# Wattuino-RC_v10.net
KiCad netlist of a schematic drawn in EAGLE
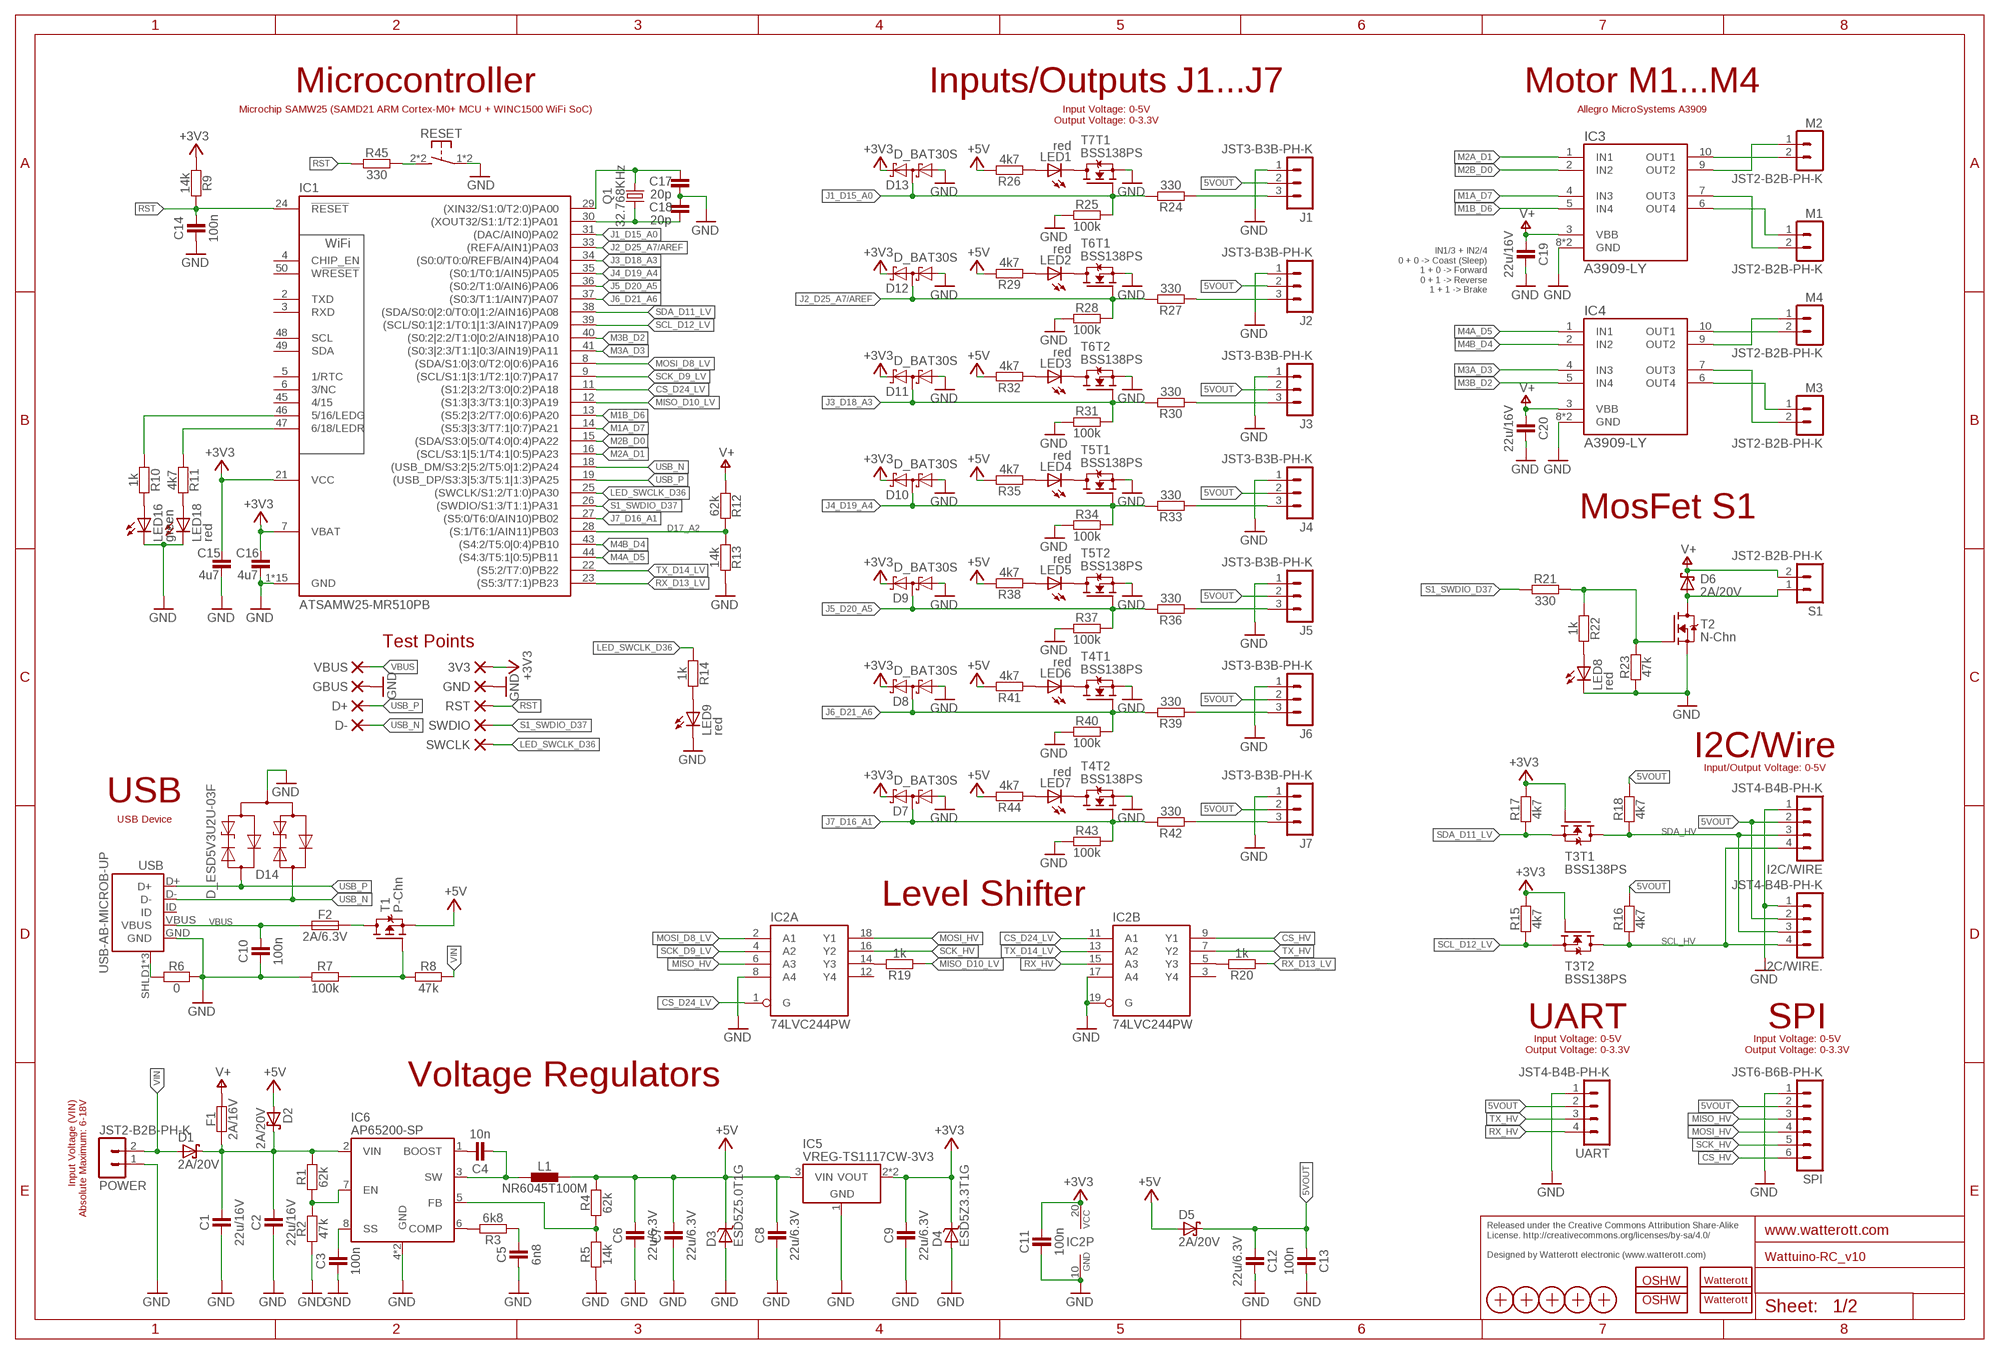
[diagram p0: schematic, sheet 1]
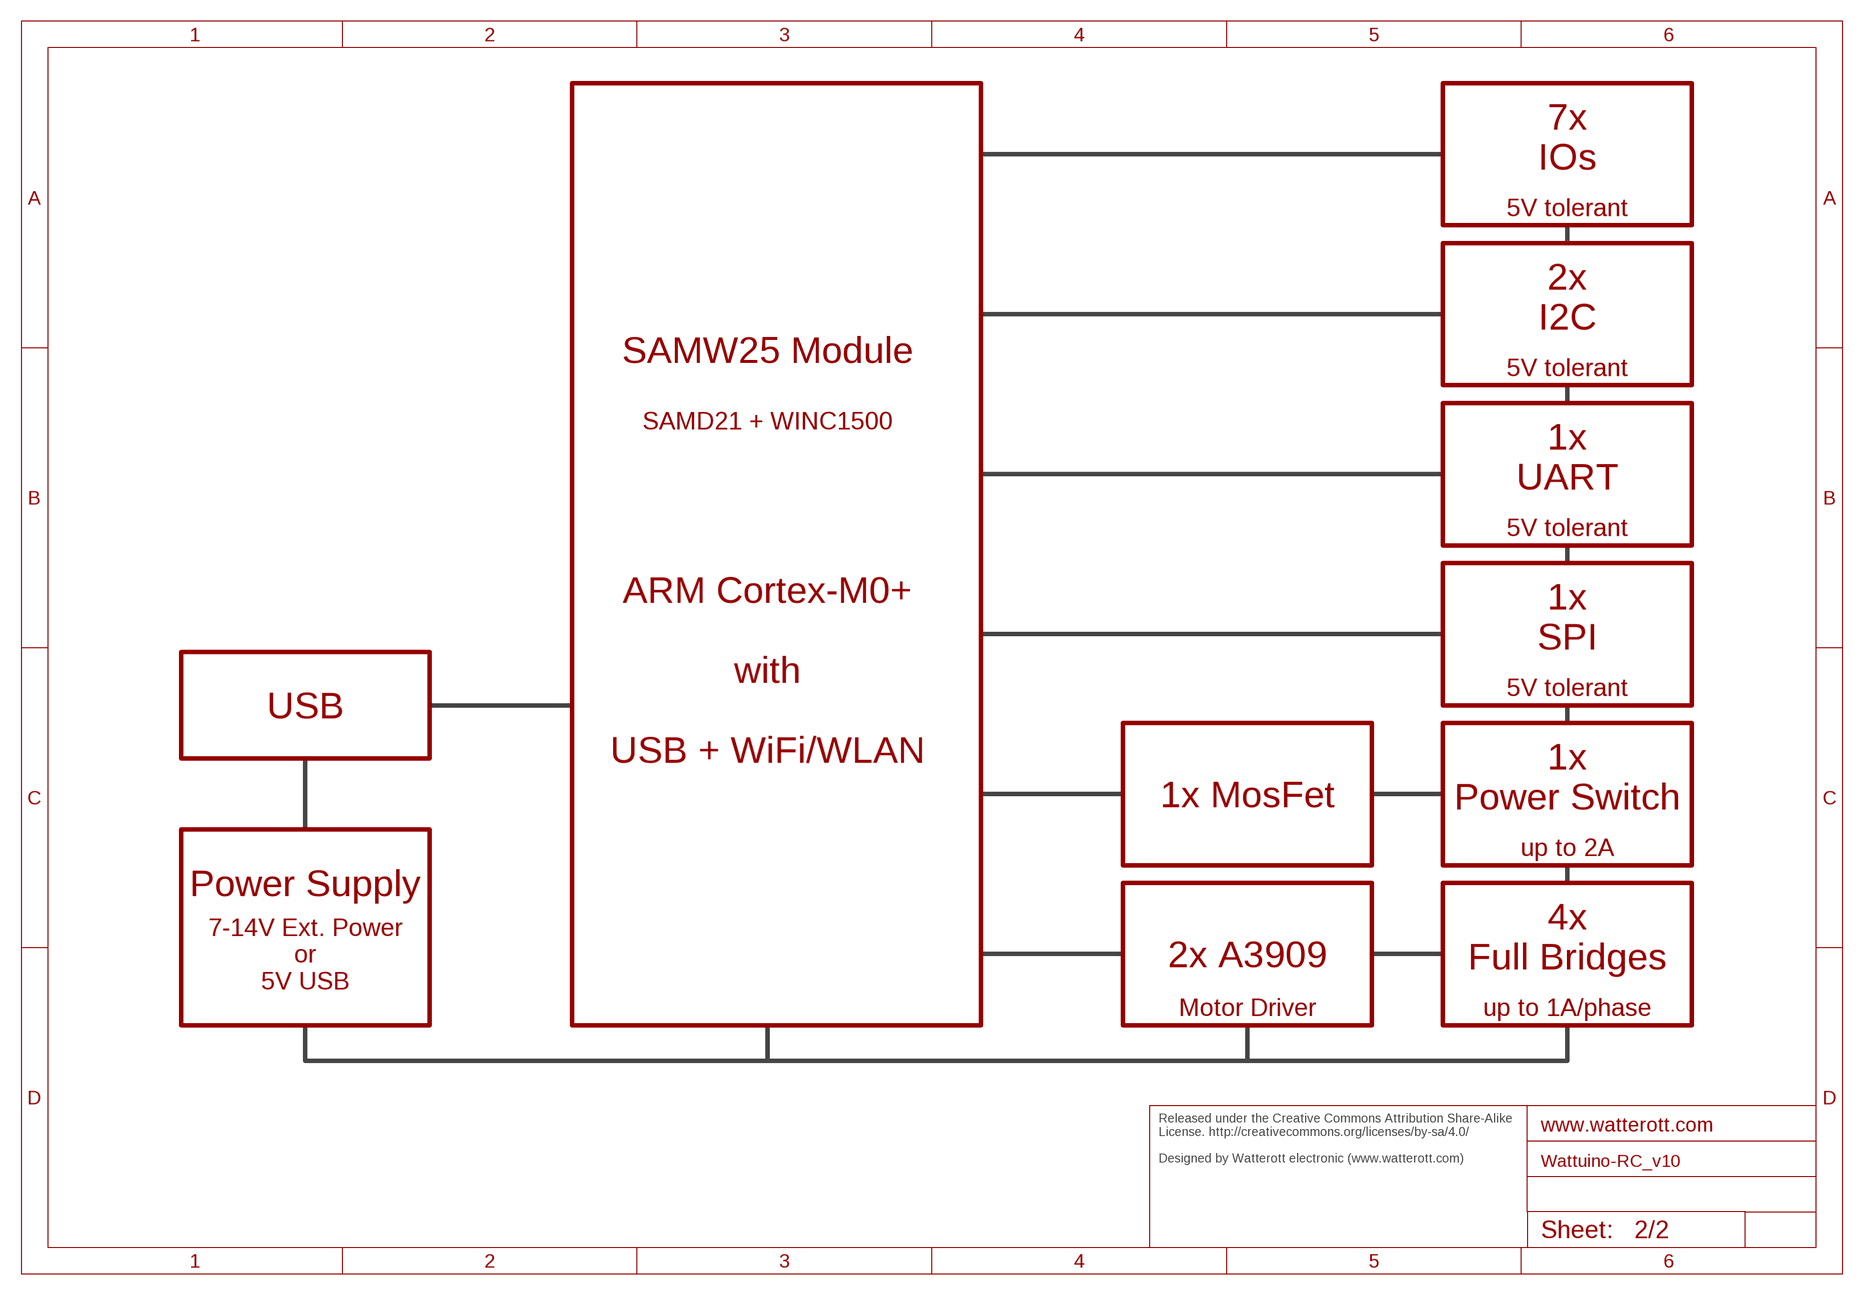
[diagram p1: schematic, sheet 2]

(export (version "E")
  (design (tool "Eeschema 10.0.6"))
  (components
    (comp (ref "3V3")
      (value "PAD-1.0_NC")
      (footprint "eagle-import:PAD-1.0_NC")
      (libsource (lib "eagle-import") (part "PAD-1.0_NC"))
    )
    (comp (ref "C1")
      (value "22u/16V")
      (footprint "eagle-import:C0805")
      (libsource (lib "eagle-import") (part "CAPACITOR-0805"))
    )
    (comp (ref "C2")
      (value "22u/16V")
      (footprint "eagle-import:C0805")
      (libsource (lib "eagle-import") (part "CAPACITOR-0805"))
    )
    (comp (ref "C3")
      (value "100n")
      (footprint "eagle-import:C0402")
      (libsource (lib "eagle-import") (part "CAPACITOR-0402"))
    )
    (comp (ref "C4")
      (value "10n")
      (footprint "eagle-import:C0402")
      (libsource (lib "eagle-import") (part "CAPACITOR-0402"))
    )
    (comp (ref "C5")
      (value "6n8")
      (footprint "eagle-import:C0402")
      (libsource (lib "eagle-import") (part "CAPACITOR-0402"))
    )
    (comp (ref "C6")
      (value "22u/6.3V")
      (footprint "eagle-import:C0805")
      (libsource (lib "eagle-import") (part "CAPACITOR-0805"))
    )
    (comp (ref "C7")
      (value "22u/6.3V")
      (footprint "eagle-import:C0805")
      (libsource (lib "eagle-import") (part "CAPACITOR-0805"))
    )
    (comp (ref "C8")
      (value "22u/6.3V")
      (footprint "eagle-import:C0805")
      (libsource (lib "eagle-import") (part "CAPACITOR-0805"))
    )
    (comp (ref "C9")
      (value "22u/6.3V")
      (footprint "eagle-import:C0805")
      (libsource (lib "eagle-import") (part "CAPACITOR-0805"))
    )
    (comp (ref "C10")
      (value "100n")
      (footprint "eagle-import:C0402")
      (libsource (lib "eagle-import") (part "CAPACITOR-0402"))
    )
    (comp (ref "C11")
      (value "100n")
      (footprint "eagle-import:C0402")
      (libsource (lib "eagle-import") (part "CAPACITOR-0402"))
    )
    (comp (ref "C12")
      (value "22u/6.3V")
      (footprint "eagle-import:C0805")
      (libsource (lib "eagle-import") (part "CAPACITOR-0805"))
    )
    (comp (ref "C13")
      (value "100n")
      (footprint "eagle-import:C0402")
      (libsource (lib "eagle-import") (part "CAPACITOR-0402"))
    )
    (comp (ref "C14")
      (value "100n")
      (footprint "eagle-import:C0402")
      (libsource (lib "eagle-import") (part "CAPACITOR-0402"))
    )
    (comp (ref "C15")
      (value "4u7")
      (footprint "eagle-import:C0603")
      (libsource (lib "eagle-import") (part "CAPACITOR-0603"))
    )
    (comp (ref "C16")
      (value "4u7")
      (footprint "eagle-import:C0603")
      (libsource (lib "eagle-import") (part "CAPACITOR-0603"))
    )
    (comp (ref "C17")
      (value "20p")
      (footprint "eagle-import:C0402")
      (libsource (lib "eagle-import") (part "CAPACITOR-0402"))
    )
    (comp (ref "C18")
      (value "20p")
      (footprint "eagle-import:C0402")
      (libsource (lib "eagle-import") (part "CAPACITOR-0402"))
    )
    (comp (ref "C19")
      (value "22u/16V")
      (footprint "eagle-import:C0805")
      (libsource (lib "eagle-import") (part "CAPACITOR-0805"))
    )
    (comp (ref "C20")
      (value "22u/16V")
      (footprint "eagle-import:C0805")
      (libsource (lib "eagle-import") (part "CAPACITOR-0805"))
    )
    (comp (ref "D+")
      (value "PAD-1.0_NC")
      (footprint "eagle-import:PAD-1.0_NC")
      (libsource (lib "eagle-import") (part "PAD-1.0_NC"))
    )
    (comp (ref "D-")
      (value "PAD-1.0_NC")
      (footprint "eagle-import:PAD-1.0_NC")
      (libsource (lib "eagle-import") (part "PAD-1.0_NC"))
    )
    (comp (ref "D1")
      (value "2A/20V")
      (footprint "eagle-import:SMA_DO214AC")
      (libsource (lib "eagle-import") (part "D_SCHOTTKY-SMA"))
    )
    (comp (ref "D2")
      (value "2A/20V")
      (footprint "eagle-import:SMA_DO214AC")
      (libsource (lib "eagle-import") (part "D_SCHOTTKY-SMA"))
    )
    (comp (ref "D3")
      (value "ESD5Z5.0T1G")
      (footprint "eagle-import:SOD523")
      (libsource (lib "eagle-import") (part "D_TVS-SOD523"))
    )
    (comp (ref "D4")
      (value "ESD5Z3.3T1G")
      (footprint "eagle-import:SOD523")
      (libsource (lib "eagle-import") (part "D_TVS-SOD523"))
    )
    (comp (ref "D5")
      (value "2A/20V")
      (footprint "eagle-import:SMA_DO214AC")
      (libsource (lib "eagle-import") (part "D_SCHOTTKY-SMA"))
    )
    (comp (ref "D6")
      (value "2A/20V")
      (footprint "eagle-import:SMA_DO214AC")
      (libsource (lib "eagle-import") (part "D_SCHOTTKY-SMA"))
    )
    (comp (ref "D7")
      (value "D_BAT30S")
      (footprint "eagle-import:SOT323")
      (libsource (lib "eagle-import") (part "D_BAT30S"))
    )
    (comp (ref "D8")
      (value "D_BAT30S")
      (footprint "eagle-import:SOT323")
      (libsource (lib "eagle-import") (part "D_BAT30S"))
    )
    (comp (ref "D9")
      (value "D_BAT30S")
      (footprint "eagle-import:SOT323")
      (libsource (lib "eagle-import") (part "D_BAT30S"))
    )
    (comp (ref "D10")
      (value "D_BAT30S")
      (footprint "eagle-import:SOT323")
      (libsource (lib "eagle-import") (part "D_BAT30S"))
    )
    (comp (ref "D11")
      (value "D_BAT30S")
      (footprint "eagle-import:SOT323")
      (libsource (lib "eagle-import") (part "D_BAT30S"))
    )
    (comp (ref "D12")
      (value "D_BAT30S")
      (footprint "eagle-import:SOT323")
      (libsource (lib "eagle-import") (part "D_BAT30S"))
    )
    (comp (ref "D13")
      (value "D_BAT30S")
      (footprint "eagle-import:SOT323")
      (libsource (lib "eagle-import") (part "D_BAT30S"))
    )
    (comp (ref "D14")
      (value "D_ESD5V3U2U-03F")
      (footprint "eagle-import:SOT723")
      (libsource (lib "eagle-import") (part "D_ESD5V3U2U-03F"))
    )
    (comp (ref "F1")
      (value "2A/16V")
      (footprint "eagle-import:C1812")
      (libsource (lib "eagle-import") (part "FUSE-1812"))
    )
    (comp (ref "F2")
      (value "2A/6.3V")
      (footprint "eagle-import:C1206")
      (libsource (lib "eagle-import") (part "FUSE-1206"))
    )
    (comp (ref "GBUS")
      (value "PAD-1.0_NC")
      (footprint "eagle-import:PAD-1.0_NC")
      (libsource (lib "eagle-import") (part "PAD-1.0_NC"))
    )
    (comp (ref "GND")
      (value "PAD-1.0_NC")
      (footprint "eagle-import:PAD-1.0_NC")
      (libsource (lib "eagle-import") (part "PAD-1.0_NC"))
    )
    (comp (ref "I2C/WIRE")
      (value "JST4-B4B-PH-K")
      (footprint "eagle-import:JST_B4B-PH-K")
      (libsource (lib "eagle-import") (part "JST4-B4B-PH-K"))
    )
    (comp (ref "I2C/WIRE.")
      (value "JST4-B4B-PH-K")
      (footprint "eagle-import:JST_B4B-PH-K")
      (libsource (lib "eagle-import") (part "JST4-B4B-PH-K"))
    )
    (comp (ref "IC1")
      (value "ATSAMW25-MR510PB")
      (footprint "eagle-import:ATSAMW25-MRX10")
      (libsource (lib "eagle-import") (part "ATSAMW25-MR510PB"))
    )
    (comp (ref "IC2")
      (value "74LVC244PW")
      (footprint "eagle-import:TSSOP20")
      (libsource (lib "eagle-import") (part "74244PWLVC"))
    )
    (comp (ref "IC3")
      (value "A3909-LY")
      (footprint "eagle-import:MSOP10-PAD")
      (libsource (lib "eagle-import") (part "A3909-LY"))
    )
    (comp (ref "IC4")
      (value "A3909-LY")
      (footprint "eagle-import:MSOP10-PAD")
      (libsource (lib "eagle-import") (part "A3909-LY"))
    )
    (comp (ref "IC5")
      (value "VREG-TS1117CW-3V3")
      (footprint "eagle-import:SOT223")
      (libsource (lib "eagle-import") (part "VREG-TS1117CW-3V3"))
    )
    (comp (ref "IC6")
      (value "AP65200-SP")
      (footprint "eagle-import:SO08-PAD")
      (libsource (lib "eagle-import") (part "AP65200-SP"))
    )
    (comp (ref "J1")
      (value "JST3-B3B-PH-K")
      (footprint "eagle-import:JST_B3B-PH-K")
      (libsource (lib "eagle-import") (part "JST3-B3B-PH-K"))
    )
    (comp (ref "J2")
      (value "JST3-B3B-PH-K")
      (footprint "eagle-import:JST_B3B-PH-K")
      (libsource (lib "eagle-import") (part "JST3-B3B-PH-K"))
    )
    (comp (ref "J3")
      (value "JST3-B3B-PH-K")
      (footprint "eagle-import:JST_B3B-PH-K")
      (libsource (lib "eagle-import") (part "JST3-B3B-PH-K"))
    )
    (comp (ref "J4")
      (value "JST3-B3B-PH-K")
      (footprint "eagle-import:JST_B3B-PH-K")
      (libsource (lib "eagle-import") (part "JST3-B3B-PH-K"))
    )
    (comp (ref "J5")
      (value "JST3-B3B-PH-K")
      (footprint "eagle-import:JST_B3B-PH-K")
      (libsource (lib "eagle-import") (part "JST3-B3B-PH-K"))
    )
    (comp (ref "J6")
      (value "JST3-B3B-PH-K")
      (footprint "eagle-import:JST_B3B-PH-K")
      (libsource (lib "eagle-import") (part "JST3-B3B-PH-K"))
    )
    (comp (ref "J7")
      (value "JST3-B3B-PH-K")
      (footprint "eagle-import:JST_B3B-PH-K")
      (libsource (lib "eagle-import") (part "JST3-B3B-PH-K"))
    )
    (comp (ref "L1")
      (value "NR6045T100M")
      (footprint "eagle-import:L_NR60XX")
      (libsource (lib "eagle-import") (part "INDUCTOR-NR60XX"))
    )
    (comp (ref "LED1")
      (value "red")
      (footprint "eagle-import:C0603")
      (libsource (lib "eagle-import") (part "LED-0603"))
    )
    (comp (ref "LED2")
      (value "red")
      (footprint "eagle-import:C0603")
      (libsource (lib "eagle-import") (part "LED-0603"))
    )
    (comp (ref "LED3")
      (value "red")
      (footprint "eagle-import:C0603")
      (libsource (lib "eagle-import") (part "LED-0603"))
    )
    (comp (ref "LED4")
      (value "red")
      (footprint "eagle-import:C0603")
      (libsource (lib "eagle-import") (part "LED-0603"))
    )
    (comp (ref "LED5")
      (value "red")
      (footprint "eagle-import:C0603")
      (libsource (lib "eagle-import") (part "LED-0603"))
    )
    (comp (ref "LED6")
      (value "red")
      (footprint "eagle-import:C0603")
      (libsource (lib "eagle-import") (part "LED-0603"))
    )
    (comp (ref "LED7")
      (value "red")
      (footprint "eagle-import:C0603")
      (libsource (lib "eagle-import") (part "LED-0603"))
    )
    (comp (ref "LED8")
      (value "red")
      (footprint "eagle-import:C0603")
      (libsource (lib "eagle-import") (part "LED-0603"))
    )
    (comp (ref "LED9")
      (value "red")
      (footprint "eagle-import:C0603")
      (libsource (lib "eagle-import") (part "LED-0603"))
    )
    (comp (ref "LED16")
      (value "green")
      (footprint "eagle-import:C0603")
      (libsource (lib "eagle-import") (part "LED-0603"))
    )
    (comp (ref "LED18")
      (value "red")
      (footprint "eagle-import:C0603")
      (libsource (lib "eagle-import") (part "LED-0603"))
    )
    (comp (ref "LOGO1")
      (value "OSHW_LOGOX0100")
      (footprint "eagle-import:OSHW_6X100")
      (libsource (lib "eagle-import") (part "OSHW_LOGOX0100"))
    )
    (comp (ref "LOGO2")
      (value "OSHW_LOGOX0150")
      (footprint "eagle-import:OSHW_6X150")
      (libsource (lib "eagle-import") (part "OSHW_LOGOX0150"))
    )
    (comp (ref "LOGO3")
      (value "LOGO-S_PLACE_S")
      (footprint "eagle-import:SPARK_TPLACE_S")
      (libsource (lib "eagle-import") (part "LOGO-S_PLACE_S"))
    )
    (comp (ref "LOGO4")
      (value "LOGO-PLACE")
      (footprint "eagle-import:LOGO_TPLACE")
      (libsource (lib "eagle-import") (part "LOGO-PLACE"))
    )
    (comp (ref "M1")
      (value "JST2-B2B-PH-K")
      (footprint "eagle-import:JST_B2B-PH-K")
      (libsource (lib "eagle-import") (part "JST2-B2B-PH-K"))
    )
    (comp (ref "M2")
      (value "JST2-B2B-PH-K")
      (footprint "eagle-import:JST_B2B-PH-K")
      (libsource (lib "eagle-import") (part "JST2-B2B-PH-K"))
    )
    (comp (ref "M3")
      (value "JST2-B2B-PH-K")
      (footprint "eagle-import:JST_B2B-PH-K")
      (libsource (lib "eagle-import") (part "JST2-B2B-PH-K"))
    )
    (comp (ref "M4")
      (value "JST2-B2B-PH-K")
      (footprint "eagle-import:JST_B2B-PH-K")
      (libsource (lib "eagle-import") (part "JST2-B2B-PH-K"))
    )
    (comp (ref "POWER")
      (value "JST2-B2B-PH-K")
      (footprint "eagle-import:JST_B2B-PH-K")
      (libsource (lib "eagle-import") (part "JST2-B2B-PH-K"))
    )
    (comp (ref "Q1")
      (value "32.768KHz")
      (footprint "eagle-import:CRYSTAL_ZM315")
      (libsource (lib "eagle-import") (part "CRYSTAL-ZM315"))
    )
    (comp (ref "R1")
      (value "62k")
      (footprint "eagle-import:C0402")
      (libsource (lib "eagle-import") (part "RESISTOR-0402"))
    )
    (comp (ref "R2")
      (value "47k")
      (footprint "eagle-import:C0402")
      (libsource (lib "eagle-import") (part "RESISTOR-0402"))
    )
    (comp (ref "R3")
      (value "6k8")
      (footprint "eagle-import:C0402")
      (libsource (lib "eagle-import") (part "RESISTOR-0402"))
    )
    (comp (ref "R4")
      (value "62k")
      (footprint "eagle-import:C0402")
      (libsource (lib "eagle-import") (part "RESISTOR-0402"))
    )
    (comp (ref "R5")
      (value "14k")
      (footprint "eagle-import:C0402")
      (libsource (lib "eagle-import") (part "RESISTOR-0402"))
    )
    (comp (ref "R6")
      (value "0")
      (footprint "eagle-import:C0402")
      (libsource (lib "eagle-import") (part "RESISTOR-0402"))
    )
    (comp (ref "R7")
      (value "100k")
      (footprint "eagle-import:C0402")
      (libsource (lib "eagle-import") (part "RESISTOR-0402"))
    )
    (comp (ref "R8")
      (value "47k")
      (footprint "eagle-import:C0402")
      (libsource (lib "eagle-import") (part "RESISTOR-0402"))
    )
    (comp (ref "R9")
      (value "14k")
      (footprint "eagle-import:C0402")
      (libsource (lib "eagle-import") (part "RESISTOR-0402"))
    )
    (comp (ref "R10")
      (value "1k")
      (footprint "eagle-import:C0402")
      (libsource (lib "eagle-import") (part "RESISTOR-0402"))
    )
    (comp (ref "R11")
      (value "4k7")
      (footprint "eagle-import:C0402")
      (libsource (lib "eagle-import") (part "RESISTOR-0402"))
    )
    (comp (ref "R12")
      (value "62k")
      (footprint "eagle-import:C0402")
      (libsource (lib "eagle-import") (part "RESISTOR-0402"))
    )
    (comp (ref "R13")
      (value "14k")
      (footprint "eagle-import:C0402")
      (libsource (lib "eagle-import") (part "RESISTOR-0402"))
    )
    (comp (ref "R14")
      (value "1k")
      (footprint "eagle-import:C0402")
      (libsource (lib "eagle-import") (part "RESISTOR-0402"))
    )
    (comp (ref "R15")
      (value "4k7")
      (footprint "eagle-import:C0402")
      (libsource (lib "eagle-import") (part "RESISTOR-0402"))
    )
    (comp (ref "R16")
      (value "4k7")
      (footprint "eagle-import:C0402")
      (libsource (lib "eagle-import") (part "RESISTOR-0402"))
    )
    (comp (ref "R17")
      (value "4k7")
      (footprint "eagle-import:C0402")
      (libsource (lib "eagle-import") (part "RESISTOR-0402"))
    )
    (comp (ref "R18")
      (value "4k7")
      (footprint "eagle-import:C0402")
      (libsource (lib "eagle-import") (part "RESISTOR-0402"))
    )
    (comp (ref "R19")
      (value "1k")
      (footprint "eagle-import:C0402")
      (libsource (lib "eagle-import") (part "RESISTOR-0402"))
    )
    (comp (ref "R20")
      (value "1k")
      (footprint "eagle-import:C0402")
      (libsource (lib "eagle-import") (part "RESISTOR-0402"))
    )
    (comp (ref "R21")
      (value "330")
      (footprint "eagle-import:C0402")
      (libsource (lib "eagle-import") (part "RESISTOR-0402"))
    )
    (comp (ref "R22")
      (value "1k")
      (footprint "eagle-import:C0402")
      (libsource (lib "eagle-import") (part "RESISTOR-0402"))
    )
    (comp (ref "R23")
      (value "47k")
      (footprint "eagle-import:C0402")
      (libsource (lib "eagle-import") (part "RESISTOR-0402"))
    )
    (comp (ref "R24")
      (value "330")
      (footprint "eagle-import:C0402")
      (libsource (lib "eagle-import") (part "RESISTOR-0402"))
    )
    (comp (ref "R25")
      (value "100k")
      (footprint "eagle-import:C0402")
      (libsource (lib "eagle-import") (part "RESISTOR-0402"))
    )
    (comp (ref "R26")
      (value "4k7")
      (footprint "eagle-import:C0402")
      (libsource (lib "eagle-import") (part "RESISTOR-0402"))
    )
    (comp (ref "R27")
      (value "330")
      (footprint "eagle-import:C0402")
      (libsource (lib "eagle-import") (part "RESISTOR-0402"))
    )
    (comp (ref "R28")
      (value "100k")
      (footprint "eagle-import:C0402")
      (libsource (lib "eagle-import") (part "RESISTOR-0402"))
    )
    (comp (ref "R29")
      (value "4k7")
      (footprint "eagle-import:C0402")
      (libsource (lib "eagle-import") (part "RESISTOR-0402"))
    )
    (comp (ref "R30")
      (value "330")
      (footprint "eagle-import:C0402")
      (libsource (lib "eagle-import") (part "RESISTOR-0402"))
    )
    (comp (ref "R31")
      (value "100k")
      (footprint "eagle-import:C0402")
      (libsource (lib "eagle-import") (part "RESISTOR-0402"))
    )
    (comp (ref "R32")
      (value "4k7")
      (footprint "eagle-import:C0402")
      (libsource (lib "eagle-import") (part "RESISTOR-0402"))
    )
    (comp (ref "R33")
      (value "330")
      (footprint "eagle-import:C0402")
      (libsource (lib "eagle-import") (part "RESISTOR-0402"))
    )
    (comp (ref "R34")
      (value "100k")
      (footprint "eagle-import:C0402")
      (libsource (lib "eagle-import") (part "RESISTOR-0402"))
    )
    (comp (ref "R35")
      (value "4k7")
      (footprint "eagle-import:C0402")
      (libsource (lib "eagle-import") (part "RESISTOR-0402"))
    )
    (comp (ref "R36")
      (value "330")
      (footprint "eagle-import:C0402")
      (libsource (lib "eagle-import") (part "RESISTOR-0402"))
    )
    (comp (ref "R37")
      (value "100k")
      (footprint "eagle-import:C0402")
      (libsource (lib "eagle-import") (part "RESISTOR-0402"))
    )
    (comp (ref "R38")
      (value "4k7")
      (footprint "eagle-import:C0402")
      (libsource (lib "eagle-import") (part "RESISTOR-0402"))
    )
    (comp (ref "R39")
      (value "330")
      (footprint "eagle-import:C0402")
      (libsource (lib "eagle-import") (part "RESISTOR-0402"))
    )
    (comp (ref "R40")
      (value "100k")
      (footprint "eagle-import:C0402")
      (libsource (lib "eagle-import") (part "RESISTOR-0402"))
    )
    (comp (ref "R41")
      (value "4k7")
      (footprint "eagle-import:C0402")
      (libsource (lib "eagle-import") (part "RESISTOR-0402"))
    )
    (comp (ref "R42")
      (value "330")
      (footprint "eagle-import:C0402")
      (libsource (lib "eagle-import") (part "RESISTOR-0402"))
    )
    (comp (ref "R43")
      (value "100k")
      (footprint "eagle-import:C0402")
      (libsource (lib "eagle-import") (part "RESISTOR-0402"))
    )
    (comp (ref "R44")
      (value "4k7")
      (footprint "eagle-import:C0402")
      (libsource (lib "eagle-import") (part "RESISTOR-0402"))
    )
    (comp (ref "R45")
      (value "330")
      (footprint "eagle-import:C0402")
      (libsource (lib "eagle-import") (part "RESISTOR-0402"))
    )
    (comp (ref "RESET")
      (value "SW-TACTILE-TL3305C")
      (footprint "eagle-import:TL3305")
      (fields (field (name "MPN") "TL3305C"))
      (libsource (lib "eagle-import") (part "SW-TACTILE-TL3305"))
    )
    (comp (ref "RST")
      (value "PAD-1.0_NC")
      (footprint "eagle-import:PAD-1.0_NC")
      (libsource (lib "eagle-import") (part "PAD-1.0_NC"))
    )
    (comp (ref "S1")
      (value "JST2-B2B-PH-K")
      (footprint "eagle-import:JST_B2B-PH-K")
      (libsource (lib "eagle-import") (part "JST2-B2B-PH-K"))
    )
    (comp (ref "SPI")
      (value "JST6-B6B-PH-K")
      (footprint "eagle-import:JST_B6B-PH-K")
      (libsource (lib "eagle-import") (part "JST6-B6B-PH-K"))
    )
    (comp (ref "SWCLK")
      (value "PAD-1.0_NC")
      (footprint "eagle-import:PAD-1.0_NC")
      (libsource (lib "eagle-import") (part "PAD-1.0_NC"))
    )
    (comp (ref "SWDIO")
      (value "PAD-1.0_NC")
      (footprint "eagle-import:PAD-1.0_NC")
      (libsource (lib "eagle-import") (part "PAD-1.0_NC"))
    )
    (comp (ref "T1")
      (value "P-Chn")
      (footprint "eagle-import:SOT23")
      (libsource (lib "eagle-import") (part "MOSFET-P-SOT23"))
    )
    (comp (ref "T2")
      (value "N-Chn")
      (footprint "eagle-import:SOT23")
      (libsource (lib "eagle-import") (part "MOSFET-N-SOT23"))
    )
    (comp (ref "T3")
      (value "BSS138PS")
      (footprint "eagle-import:SOT363")
      (libsource (lib "eagle-import") (part "BSS138PS"))
    )
    (comp (ref "T4")
      (value "BSS138PS")
      (footprint "eagle-import:SOT363")
      (libsource (lib "eagle-import") (part "BSS138PS"))
    )
    (comp (ref "T5")
      (value "BSS138PS")
      (footprint "eagle-import:SOT363")
      (libsource (lib "eagle-import") (part "BSS138PS"))
    )
    (comp (ref "T6")
      (value "BSS138PS")
      (footprint "eagle-import:SOT363")
      (libsource (lib "eagle-import") (part "BSS138PS"))
    )
    (comp (ref "T7")
      (value "BSS138PS")
      (footprint "eagle-import:SOT363")
      (libsource (lib "eagle-import") (part "BSS138PS"))
    )
    (comp (ref "UART")
      (value "JST4-B4B-PH-K")
      (footprint "eagle-import:JST_B4B-PH-K")
      (libsource (lib "eagle-import") (part "JST4-B4B-PH-K"))
    )
    (comp (ref "USB")
      (value "USB-AB-MICROB-UP")
      (footprint "eagle-import:USB-MICROB-1051330011")
      (libsource (lib "eagle-import") (part "USB-AB-MICROB-UP"))
    )
    (comp (ref "VBUS")
      (value "PAD-1.0_NC")
      (footprint "eagle-import:PAD-1.0_NC")
      (libsource (lib "eagle-import") (part "PAD-1.0_NC"))
    )
    (comp (ref "X1")
      (value "PASSER-07")
      (footprint "eagle-import:PASSER_07MM")
      (libsource (lib "eagle-import") (part "PASSER-07"))
    )
    (comp (ref "X2")
      (value "PASSER-07")
      (footprint "eagle-import:PASSER_07MM")
      (libsource (lib "eagle-import") (part "PASSER-07"))
    )
    (comp (ref "X3")
      (value "PASSER-07")
      (footprint "eagle-import:PASSER_07MM")
      (libsource (lib "eagle-import") (part "PASSER-07"))
    )
    (comp (ref "X4")
      (value "PASSER-07")
      (footprint "eagle-import:PASSER_07MM")
      (libsource (lib "eagle-import") (part "PASSER-07"))
    )
    (comp (ref "X5")
      (value "PASSER-04")
      (footprint "eagle-import:PASSER_04MM")
      (libsource (lib "eagle-import") (part "PASSER-04"))
    )
  )
  (nets
    (net (code "1") (name "+3V3") (class "Default")
      (node (ref "3V3") (pin "1") (pinfunction "P_1") (pintype "passive"))
      (node (ref "C11") (pin "2") (pinfunction "2_2") (pintype "passive"))
      (node (ref "C15") (pin "2") (pinfunction "2_2") (pintype "passive"))
      (node (ref "C16") (pin "2") (pinfunction "2_2") (pintype "passive"))
      (node (ref "C9") (pin "2") (pinfunction "2_2") (pintype "passive"))
      (node (ref "D10") (pin "2") (pinfunction "C_2") (pintype "passive"))
      (node (ref "D11") (pin "2") (pinfunction "C_2") (pintype "passive"))
      (node (ref "D12") (pin "2") (pinfunction "C_2") (pintype "passive"))
      (node (ref "D13") (pin "2") (pinfunction "C_2") (pintype "passive"))
      (node (ref "D4") (pin "C") (pinfunction "C_C") (pintype "passive"))
      (node (ref "D7") (pin "2") (pinfunction "C_2") (pintype "passive"))
      (node (ref "D8") (pin "2") (pinfunction "C_2") (pintype "passive"))
      (node (ref "D9") (pin "2") (pinfunction "C_2") (pintype "passive"))
      (node (ref "IC1") (pin "21") (pinfunction "VCC_21") (pintype "power_in"))
      (node (ref "IC1") (pin "7") (pinfunction "VBAT_7") (pintype "power_in"))
      (node (ref "IC2") (pin "20") (pinfunction "VCC_20") (pintype "power_in"))
      (node (ref "IC5") (pin "2") (pinfunction "VOUT_2") (pintype "power_in"))
      (node (ref "IC5") (pin "4") (pinfunction "VOUT_4") (pintype "power_in"))
      (node (ref "R15") (pin "2") (pinfunction "2_2") (pintype "passive"))
      (node (ref "R17") (pin "2") (pinfunction "2_2") (pintype "passive"))
      (node (ref "R9") (pin "1") (pinfunction "1_1") (pintype "passive"))
      (node (ref "T3") (pin "2") (pinfunction "G_2") (pintype "passive"))
      (node (ref "T3") (pin "5") (pinfunction "G_5") (pintype "passive"))
    )
    (net (code "2") (name "+5V") (class "Default")
      (node (ref "C6") (pin "2") (pinfunction "2_2") (pintype "passive"))
      (node (ref "C7") (pin "2") (pinfunction "2_2") (pintype "passive"))
      (node (ref "C8") (pin "2") (pinfunction "2_2") (pintype "passive"))
      (node (ref "D2") (pin "A") (pinfunction "A_A") (pintype "passive"))
      (node (ref "D3") (pin "C") (pinfunction "C_C") (pintype "passive"))
      (node (ref "D5") (pin "A") (pinfunction "A_A") (pintype "passive"))
      (node (ref "IC5") (pin "3") (pinfunction "VIN_3") (pintype "power_in"))
      (node (ref "L1") (pin "2") (pinfunction "2_2") (pintype "passive"))
      (node (ref "R26") (pin "2") (pinfunction "2_2") (pintype "passive"))
      (node (ref "R29") (pin "2") (pinfunction "2_2") (pintype "passive"))
      (node (ref "R32") (pin "2") (pinfunction "2_2") (pintype "passive"))
      (node (ref "R35") (pin "2") (pinfunction "2_2") (pintype "passive"))
      (node (ref "R38") (pin "2") (pinfunction "2_2") (pintype "passive"))
      (node (ref "R4") (pin "2") (pinfunction "2_2") (pintype "passive"))
      (node (ref "R41") (pin "2") (pinfunction "2_2") (pintype "passive"))
      (node (ref "R44") (pin "2") (pinfunction "2_2") (pintype "passive"))
      (node (ref "T1") (pin "2") (pinfunction "S_2") (pintype "passive"))
    )
    (net (code "3") (name "5VOUT") (class "Default")
      (node (ref "C12") (pin "2") (pinfunction "2_2") (pintype "passive"))
      (node (ref "C13") (pin "2") (pinfunction "2_2") (pintype "passive"))
      (node (ref "D5") (pin "C") (pinfunction "C_C") (pintype "passive"))
      (node (ref "I2C/WIRE") (pin "2") (pinfunction "2_2") (pintype "passive"))
      (node (ref "I2C/WIRE.") (pin "2") (pinfunction "2_2") (pintype "passive"))
      (node (ref "J1") (pin "2") (pinfunction "2_2") (pintype "passive"))
      (node (ref "J2") (pin "2") (pinfunction "2_2") (pintype "passive"))
      (node (ref "J3") (pin "2") (pinfunction "2_2") (pintype "passive"))
      (node (ref "J4") (pin "2") (pinfunction "2_2") (pintype "passive"))
      (node (ref "J5") (pin "2") (pinfunction "2_2") (pintype "passive"))
      (node (ref "J6") (pin "2") (pinfunction "2_2") (pintype "passive"))
      (node (ref "J7") (pin "2") (pinfunction "2_2") (pintype "passive"))
      (node (ref "R16") (pin "2") (pinfunction "2_2") (pintype "passive"))
      (node (ref "R18") (pin "2") (pinfunction "2_2") (pintype "passive"))
      (node (ref "SPI") (pin "2") (pinfunction "2_2") (pintype "passive"))
      (node (ref "UART") (pin "2") (pinfunction "2_2") (pintype "passive"))
    )
    (net (code "4") (name "CS_D24_LV") (class "Default")
      (node (ref "IC1") (pin "11") (pinfunction "(S1:2|3:2/T3:0|0:2)PA18_11") (pintype "bidirectional"))
      (node (ref "IC2") (pin "1") (pinfunction "G_1") (pintype "input"))
      (node (ref "IC2") (pin "11") (pinfunction "A1_11") (pintype "input"))
    )
    (net (code "5") (name "CS_HV") (class "Default")
      (node (ref "IC2") (pin "9") (pinfunction "Y1_9") (pintype "tri_state"))
      (node (ref "SPI") (pin "6") (pinfunction "6_6") (pintype "passive"))
    )
    (net (code "6") (name "D17_A2") (class "Default")
      (node (ref "IC1") (pin "28") (pinfunction "(S:1/T6:1/AIN11)PB03_28") (pintype "bidirectional"))
      (node (ref "R12") (pin "2") (pinfunction "2_2") (pintype "passive"))
      (node (ref "R13") (pin "1") (pinfunction "1_1") (pintype "passive"))
    )
    (net (code "7") (name "GND") (class "Default")
      (node (ref "C1") (pin "1") (pinfunction "1_1") (pintype "passive"))
      (node (ref "C10") (pin "1") (pinfunction "1_1") (pintype "passive"))
      (node (ref "C11") (pin "1") (pinfunction "1_1") (pintype "passive"))
      (node (ref "C12") (pin "1") (pinfunction "1_1") (pintype "passive"))
      (node (ref "C13") (pin "1") (pinfunction "1_1") (pintype "passive"))
      (node (ref "C14") (pin "1") (pinfunction "1_1") (pintype "passive"))
      (node (ref "C15") (pin "1") (pinfunction "1_1") (pintype "passive"))
      (node (ref "C16") (pin "1") (pinfunction "1_1") (pintype "passive"))
      (node (ref "C17") (pin "2") (pinfunction "2_2") (pintype "passive"))
      (node (ref "C18") (pin "2") (pinfunction "2_2") (pintype "passive"))
      (node (ref "C19") (pin "2") (pinfunction "2_2") (pintype "passive"))
      (node (ref "C2") (pin "1") (pinfunction "1_1") (pintype "passive"))
      (node (ref "C20") (pin "2") (pinfunction "2_2") (pintype "passive"))
      (node (ref "C3") (pin "1") (pinfunction "1_1") (pintype "passive"))
      (node (ref "C5") (pin "1") (pinfunction "1_1") (pintype "passive"))
      (node (ref "C6") (pin "1") (pinfunction "1_1") (pintype "passive"))
      (node (ref "C7") (pin "1") (pinfunction "1_1") (pintype "passive"))
      (node (ref "C8") (pin "1") (pinfunction "1_1") (pintype "passive"))
      (node (ref "C9") (pin "1") (pinfunction "1_1") (pintype "passive"))
      (node (ref "D10") (pin "1") (pinfunction "A_1") (pintype "passive"))
      (node (ref "D11") (pin "1") (pinfunction "A_1") (pintype "passive"))
      (node (ref "D12") (pin "1") (pinfunction "A_1") (pintype "passive"))
      (node (ref "D13") (pin "1") (pinfunction "A_1") (pintype "passive"))
      (node (ref "D14") (pin "3") (pinfunction "A_3") (pintype "passive"))
      (node (ref "D3") (pin "A") (pinfunction "A_A") (pintype "passive"))
      (node (ref "D4") (pin "A") (pinfunction "A_A") (pintype "passive"))
      (node (ref "D7") (pin "1") (pinfunction "A_1") (pintype "passive"))
      (node (ref "D8") (pin "1") (pinfunction "A_1") (pintype "passive"))
      (node (ref "D9") (pin "1") (pinfunction "A_1") (pintype "passive"))
      (node (ref "GBUS") (pin "1") (pinfunction "P_1") (pintype "passive"))
      (node (ref "GND") (pin "1") (pinfunction "P_1") (pintype "passive"))
      (node (ref "I2C/WIRE") (pin "1") (pinfunction "1_1") (pintype "passive"))
      (node (ref "I2C/WIRE.") (pin "1") (pinfunction "1_1") (pintype "passive"))
      (node (ref "IC1") (pin "1") (pinfunction "GND_1") (pintype "power_in"))
      (node (ref "IC1") (pin "10") (pinfunction "GND_10") (pintype "power_in"))
      (node (ref "IC1") (pin "17") (pinfunction "GND_17") (pintype "power_in"))
      (node (ref "IC1") (pin "20") (pinfunction "GND_20") (pintype "power_in"))
      (node (ref "IC1") (pin "32") (pinfunction "GND_32") (pintype "power_in"))
      (node (ref "IC1") (pin "42") (pinfunction "GND_42") (pintype "power_in"))
      (node (ref "IC1") (pin "51") (pinfunction "GND_51") (pintype "power_in"))
      (node (ref "IC1") (pin "GND@1") (pinfunction "GND_GND@1") (pintype "power_in"))
      (node (ref "IC1") (pin "GND@2") (pinfunction "GND_GND@2") (pintype "power_in"))
      (node (ref "IC1") (pin "GND@3") (pinfunction "GND_GND@3") (pintype "power_in"))
      (node (ref "IC1") (pin "GND@4") (pinfunction "GND_GND@4") (pintype "power_in"))
      (node (ref "IC1") (pin "GND@5") (pinfunction "GND_GND@5") (pintype "power_in"))
      (node (ref "IC1") (pin "GND@6") (pinfunction "GND_GND@6") (pintype "power_in"))
      (node (ref "IC1") (pin "GND@7") (pinfunction "GND_GND@7") (pintype "power_in"))
      (node (ref "IC1") (pin "GND@8") (pinfunction "GND_GND@8") (pintype "power_in"))
      (node (ref "IC2") (pin "10") (pinfunction "GND_10") (pintype "power_in"))
      (node (ref "IC2") (pin "17") (pinfunction "A4_17") (pintype "input"))
      (node (ref "IC2") (pin "19") (pinfunction "G_19") (pintype "input"))
      (node (ref "IC2") (pin "8") (pinfunction "A4_8") (pintype "input"))
      (node (ref "IC3") (pin "8") (pinfunction "GND_8") (pintype "power_in"))
      (node (ref "IC3") (pin "TP") (pinfunction "GND_TP") (pintype "power_in"))
      (node (ref "IC4") (pin "8") (pinfunction "GND_8") (pintype "power_in"))
      (node (ref "IC4") (pin "TP") (pinfunction "GND_TP") (pintype "power_in"))
      (node (ref "IC5") (pin "1") (pinfunction "GND_1") (pintype "power_in"))
      (node (ref "IC6") (pin "4") (pinfunction "GND_4") (pintype "power_in"))
      (node (ref "IC6") (pin "TP") (pinfunction "GND_TP") (pintype "power_in"))
      (node (ref "J1") (pin "1") (pinfunction "1_1") (pintype "passive"))
      (node (ref "J2") (pin "1") (pinfunction "1_1") (pintype "passive"))
      (node (ref "J3") (pin "1") (pinfunction "1_1") (pintype "passive"))
      (node (ref "J4") (pin "1") (pinfunction "1_1") (pintype "passive"))
      (node (ref "J5") (pin "1") (pinfunction "1_1") (pintype "passive"))
      (node (ref "J6") (pin "1") (pinfunction "1_1") (pintype "passive"))
      (node (ref "J7") (pin "1") (pinfunction "1_1") (pintype "passive"))
      (node (ref "LED16") (pin "C") (pinfunction "C_C") (pintype "passive"))
      (node (ref "LED18") (pin "C") (pinfunction "C_C") (pintype "passive"))
      (node (ref "LED8") (pin "C") (pinfunction "C_C") (pintype "passive"))
      (node (ref "LED9") (pin "C") (pinfunction "C_C") (pintype "passive"))
      (node (ref "POWER") (pin "1") (pinfunction "2_1") (pintype "passive"))
      (node (ref "R13") (pin "2") (pinfunction "2_2") (pintype "passive"))
      (node (ref "R2") (pin "1") (pinfunction "1_1") (pintype "passive"))
      (node (ref "R23") (pin "1") (pinfunction "1_1") (pintype "passive"))
      (node (ref "R25") (pin "1") (pinfunction "1_1") (pintype "passive"))
      (node (ref "R28") (pin "1") (pinfunction "1_1") (pintype "passive"))
      (node (ref "R31") (pin "1") (pinfunction "1_1") (pintype "passive"))
      (node (ref "R34") (pin "1") (pinfunction "1_1") (pintype "passive"))
      (node (ref "R37") (pin "1") (pinfunction "1_1") (pintype "passive"))
      (node (ref "R40") (pin "1") (pinfunction "1_1") (pintype "passive"))
      (node (ref "R43") (pin "1") (pinfunction "1_1") (pintype "passive"))
      (node (ref "R5") (pin "1") (pinfunction "1_1") (pintype "passive"))
      (node (ref "R6") (pin "1") (pinfunction "1_1") (pintype "passive"))
      (node (ref "R7") (pin "1") (pinfunction "1_1") (pintype "passive"))
      (node (ref "RESET") (pin "1") (pinfunction "P1_1") (pintype "passive"))
      (node (ref "RESET") (pin "4") (pinfunction "P1_4") (pintype "passive"))
      (node (ref "SPI") (pin "1") (pinfunction "1_1") (pintype "passive"))
      (node (ref "T2") (pin "2") (pinfunction "S_2") (pintype "passive"))
      (node (ref "T4") (pin "1") (pinfunction "S_1") (pintype "passive"))
      (node (ref "T4") (pin "4") (pinfunction "S_4") (pintype "passive"))
      (node (ref "T5") (pin "1") (pinfunction "S_1") (pintype "passive"))
      (node (ref "T5") (pin "4") (pinfunction "S_4") (pintype "passive"))
      (node (ref "T6") (pin "1") (pinfunction "S_1") (pintype "passive"))
      (node (ref "T6") (pin "4") (pinfunction "S_4") (pintype "passive"))
      (node (ref "T7") (pin "1") (pinfunction "S_1") (pintype "passive"))
      (node (ref "UART") (pin "1") (pinfunction "1_1") (pintype "passive"))
      (node (ref "USB") (pin "GND") (pinfunction "GND_GND") (pintype "power_in"))
    )
    (net (code "8") (name "J1_D15_A0") (class "Default")
      (node (ref "D13") (pin "3") (pinfunction "CA_3") (pintype "passive"))
      (node (ref "IC1") (pin "31") (pinfunction "(DAC/AIN0)PA02_31") (pintype "bidirectional"))
      (node (ref "R24") (pin "2") (pinfunction "2_2") (pintype "passive"))
      (node (ref "R25") (pin "2") (pinfunction "2_2") (pintype "passive"))
      (node (ref "T7") (pin "2") (pinfunction "G_2") (pintype "passive"))
    )
    (net (code "9") (name "J2_D25_A7{slash}AREF") (class "Default")
      (node (ref "D12") (pin "3") (pinfunction "CA_3") (pintype "passive"))
      (node (ref "IC1") (pin "33") (pinfunction "(REFA/AIN1)PA03_33") (pintype "bidirectional"))
      (node (ref "R27") (pin "2") (pinfunction "2_2") (pintype "passive"))
      (node (ref "R28") (pin "2") (pinfunction "2_2") (pintype "passive"))
      (node (ref "T6") (pin "2") (pinfunction "G_2") (pintype "passive"))
    )
    (net (code "10") (name "J3_D18_A3") (class "Default")
      (node (ref "D11") (pin "3") (pinfunction "CA_3") (pintype "passive"))
      (node (ref "IC1") (pin "34") (pinfunction "(S0:0/T0:0/REFB/AIN4)PA04_34") (pintype "bidirectional"))
      (node (ref "R30") (pin "2") (pinfunction "2_2") (pintype "passive"))
      (node (ref "R31") (pin "2") (pinfunction "2_2") (pintype "passive"))
      (node (ref "T6") (pin "5") (pinfunction "G_5") (pintype "passive"))
    )
    (net (code "11") (name "J4_D19_A4") (class "Default")
      (node (ref "D10") (pin "3") (pinfunction "CA_3") (pintype "passive"))
      (node (ref "IC1") (pin "35") (pinfunction "(S0:1/T0:1/AIN5)PA05_35") (pintype "bidirectional"))
      (node (ref "R33") (pin "2") (pinfunction "2_2") (pintype "passive"))
      (node (ref "R34") (pin "2") (pinfunction "2_2") (pintype "passive"))
      (node (ref "T5") (pin "2") (pinfunction "G_2") (pintype "passive"))
    )
    (net (code "12") (name "J5_D20_A5") (class "Default")
      (node (ref "D9") (pin "3") (pinfunction "CA_3") (pintype "passive"))
      (node (ref "IC1") (pin "36") (pinfunction "(S0:2/T1:0/AIN6)PA06_36") (pintype "bidirectional"))
      (node (ref "R36") (pin "2") (pinfunction "2_2") (pintype "passive"))
      (node (ref "R37") (pin "2") (pinfunction "2_2") (pintype "passive"))
      (node (ref "T5") (pin "5") (pinfunction "G_5") (pintype "passive"))
    )
    (net (code "13") (name "J6_D21_A6") (class "Default")
      (node (ref "D8") (pin "3") (pinfunction "CA_3") (pintype "passive"))
      (node (ref "IC1") (pin "37") (pinfunction "(S0:3/T1:1/AIN7)PA07_37") (pintype "bidirectional"))
      (node (ref "R39") (pin "2") (pinfunction "2_2") (pintype "passive"))
      (node (ref "R40") (pin "2") (pinfunction "2_2") (pintype "passive"))
      (node (ref "T4") (pin "2") (pinfunction "G_2") (pintype "passive"))
    )
    (net (code "14") (name "J7_D16_A1") (class "Default")
      (node (ref "D7") (pin "3") (pinfunction "CA_3") (pintype "passive"))
      (node (ref "IC1") (pin "27") (pinfunction "(S5:0/T6:0/AIN10)PB02_27") (pintype "bidirectional"))
      (node (ref "R42") (pin "2") (pinfunction "2_2") (pintype "passive"))
      (node (ref "R43") (pin "2") (pinfunction "2_2") (pintype "passive"))
      (node (ref "T4") (pin "5") (pinfunction "G_5") (pintype "passive"))
    )
    (net (code "15") (name "LED_SWCLK_D36") (class "Default")
      (node (ref "IC1") (pin "25") (pinfunction "(SWCLK/S1:2/T1:0)PA30_25") (pintype "bidirectional"))
      (node (ref "R14") (pin "1") (pinfunction "1_1") (pintype "passive"))
      (node (ref "SWCLK") (pin "1") (pinfunction "P_1") (pintype "passive"))
    )
    (net (code "16") (name "M1A_D7") (class "Default")
      (node (ref "IC1") (pin "14") (pinfunction "(S5:3|3:3/T7:1|0:7)PA21_14") (pintype "bidirectional"))
      (node (ref "IC3") (pin "4") (pinfunction "IN3_4") (pintype "bidirectional"))
    )
    (net (code "17") (name "M1B_D6") (class "Default")
      (node (ref "IC1") (pin "13") (pinfunction "(S5:2|3:2/T7:0|0:6)PA20_13") (pintype "bidirectional"))
      (node (ref "IC3") (pin "5") (pinfunction "IN4_5") (pintype "bidirectional"))
    )
    (net (code "18") (name "M2A_D1") (class "Default")
      (node (ref "IC1") (pin "16") (pinfunction "(SCL/S3:1|5:1/T4:1|0:5)PA23_16") (pintype "bidirectional"))
      (node (ref "IC3") (pin "1") (pinfunction "IN1_1") (pintype "bidirectional"))
    )
    (net (code "19") (name "M2B_D0") (class "Default")
      (node (ref "IC1") (pin "15") (pinfunction "(SDA/S3:0|5:0/T4:0|0:4)PA22_15") (pintype "bidirectional"))
      (node (ref "IC3") (pin "2") (pinfunction "IN2_2") (pintype "bidirectional"))
    )
    (net (code "20") (name "M3A_D3") (class "Default")
      (node (ref "IC1") (pin "41") (pinfunction "(S0:3|2:3/T1:1|0:3/AIN19)PA11_41") (pintype "bidirectional"))
      (node (ref "IC4") (pin "4") (pinfunction "IN3_4") (pintype "bidirectional"))
    )
    (net (code "21") (name "M3B_D2") (class "Default")
      (node (ref "IC1") (pin "40") (pinfunction "(S0:2|2:2/T1:0|0:2/AIN18)PA10_40") (pintype "bidirectional"))
      (node (ref "IC4") (pin "5") (pinfunction "IN4_5") (pintype "bidirectional"))
    )
    (net (code "22") (name "M4A_D5") (class "Default")
      (node (ref "IC1") (pin "44") (pinfunction "(S4:3/T5:1|0:5)PB11_44") (pintype "bidirectional"))
      (node (ref "IC4") (pin "1") (pinfunction "IN1_1") (pintype "bidirectional"))
    )
    (net (code "23") (name "M4B_D4") (class "Default")
      (node (ref "IC1") (pin "43") (pinfunction "(S4:2/T5:0|0:4)PB10_43") (pintype "bidirectional"))
      (node (ref "IC4") (pin "2") (pinfunction "IN2_2") (pintype "bidirectional"))
    )
    (net (code "24") (name "MISO_D10_LV") (class "Default")
      (node (ref "IC1") (pin "12") (pinfunction "(S1:3|3:3/T3:1|0:3)PA19_12") (pintype "bidirectional"))
      (node (ref "R19") (pin "1") (pinfunction "1_1") (pintype "passive"))
    )
    (net (code "25") (name "MISO_HV") (class "Default")
      (node (ref "IC2") (pin "6") (pinfunction "A3_6") (pintype "input"))
      (node (ref "SPI") (pin "3") (pinfunction "3_3") (pintype "passive"))
    )
    (net (code "26") (name "MOSI_D8_LV") (class "Default")
      (node (ref "IC1") (pin "8") (pinfunction "(SDA/S1:0|3:0/T2:0|0:6)PA16_8") (pintype "bidirectional"))
      (node (ref "IC2") (pin "2") (pinfunction "A1_2") (pintype "input"))
    )
    (net (code "27") (name "MOSI_HV") (class "Default")
      (node (ref "IC2") (pin "18") (pinfunction "Y1_18") (pintype "tri_state"))
      (node (ref "SPI") (pin "4") (pinfunction "4_4") (pintype "passive"))
    )
    (net (code "28") (name "Net-(C5-Pad2)") (class "Default")
      (node (ref "C5") (pin "2") (pinfunction "2_2") (pintype "passive"))
      (node (ref "R3") (pin "1") (pinfunction "1_1") (pintype "passive"))
    )
    (net (code "29") (name "Net-(IC1-(XIN32{slash}S1:0{slash}T2:0)PA00)") (class "Default")
      (node (ref "C17") (pin "1") (pinfunction "1_1") (pintype "passive"))
      (node (ref "IC1") (pin "29") (pinfunction "(XIN32/S1:0/T2:0)PA00_29") (pintype "bidirectional"))
      (node (ref "Q1") (pin "2") (pinfunction "2_2") (pintype "passive"))
    )
    (net (code "30") (name "Net-(IC1-(XOUT32{slash}S1:1{slash}T2:1)PA01)") (class "Default")
      (node (ref "C18") (pin "1") (pinfunction "1_1") (pintype "passive"))
      (node (ref "IC1") (pin "30") (pinfunction "(XOUT32/S1:1/T2:1)PA01_30") (pintype "bidirectional"))
      (node (ref "Q1") (pin "1") (pinfunction "1_1") (pintype "passive"))
    )
    (net (code "31") (name "Net-(IC1-5{slash}16{slash}LEDG)") (class "Default")
      (node (ref "IC1") (pin "46") (pinfunction "5/16/LEDG_46") (pintype "bidirectional"))
      (node (ref "R10") (pin "1") (pinfunction "1_1") (pintype "passive"))
    )
    (net (code "32") (name "Net-(IC1-6{slash}18{slash}LEDR)") (class "Default")
      (node (ref "IC1") (pin "47") (pinfunction "6/18/LEDR_47") (pintype "bidirectional"))
      (node (ref "R11") (pin "1") (pinfunction "1_1") (pintype "passive"))
    )
    (net (code "33") (name "Net-(IC2A-Y3)") (class "Default")
      (node (ref "IC2") (pin "14") (pinfunction "Y3_14") (pintype "tri_state"))
      (node (ref "R19") (pin "2") (pinfunction "2_2") (pintype "passive"))
    )
    (net (code "34") (name "Net-(IC2B-Y3)") (class "Default")
      (node (ref "IC2") (pin "5") (pinfunction "Y3_5") (pintype "tri_state"))
      (node (ref "R20") (pin "2") (pinfunction "2_2") (pintype "passive"))
    )
    (net (code "35") (name "Net-(IC3-OUT1)") (class "Default")
      (node (ref "IC3") (pin "10") (pinfunction "OUT1_10") (pintype "passive"))
      (node (ref "M2") (pin "2") (pinfunction "1_2") (pintype "passive"))
    )
    (net (code "36") (name "Net-(IC3-OUT2)") (class "Default")
      (node (ref "IC3") (pin "9") (pinfunction "OUT2_9") (pintype "passive"))
      (node (ref "M2") (pin "1") (pinfunction "2_1") (pintype "passive"))
    )
    (net (code "37") (name "Net-(IC3-OUT3)") (class "Default")
      (node (ref "IC3") (pin "7") (pinfunction "OUT3_7") (pintype "passive"))
      (node (ref "M1") (pin "2") (pinfunction "1_2") (pintype "passive"))
    )
    (net (code "38") (name "Net-(IC3-OUT4)") (class "Default")
      (node (ref "IC3") (pin "6") (pinfunction "OUT4_6") (pintype "passive"))
      (node (ref "M1") (pin "1") (pinfunction "2_1") (pintype "passive"))
    )
    (net (code "39") (name "Net-(IC4-OUT1)") (class "Default")
      (node (ref "IC4") (pin "10") (pinfunction "OUT1_10") (pintype "passive"))
      (node (ref "M4") (pin "2") (pinfunction "1_2") (pintype "passive"))
    )
    (net (code "40") (name "Net-(IC4-OUT2)") (class "Default")
      (node (ref "IC4") (pin "9") (pinfunction "OUT2_9") (pintype "passive"))
      (node (ref "M4") (pin "1") (pinfunction "2_1") (pintype "passive"))
    )
    (net (code "41") (name "Net-(IC4-OUT3)") (class "Default")
      (node (ref "IC4") (pin "7") (pinfunction "OUT3_7") (pintype "passive"))
      (node (ref "M3") (pin "2") (pinfunction "1_2") (pintype "passive"))
    )
    (net (code "42") (name "Net-(IC4-OUT4)") (class "Default")
      (node (ref "IC4") (pin "6") (pinfunction "OUT4_6") (pintype "passive"))
      (node (ref "M3") (pin "1") (pinfunction "2_1") (pintype "passive"))
    )
    (net (code "43") (name "Net-(IC6-BOOST)") (class "Default")
      (node (ref "C4") (pin "2") (pinfunction "2_2") (pintype "passive"))
      (node (ref "IC6") (pin "1") (pinfunction "BOOST_1") (pintype "passive"))
    )
    (net (code "44") (name "Net-(IC6-COMP)") (class "Default")
      (node (ref "IC6") (pin "6") (pinfunction "COMP_6") (pintype "passive"))
      (node (ref "R3") (pin "2") (pinfunction "2_2") (pintype "passive"))
    )
    (net (code "45") (name "Net-(IC6-EN)") (class "Default")
      (node (ref "IC6") (pin "7") (pinfunction "EN_7") (pintype "input"))
      (node (ref "R1") (pin "1") (pinfunction "1_1") (pintype "passive"))
      (node (ref "R2") (pin "2") (pinfunction "2_2") (pintype "passive"))
    )
    (net (code "46") (name "Net-(IC6-FB)") (class "Default")
      (node (ref "IC6") (pin "5") (pinfunction "FB_5") (pintype "passive"))
      (node (ref "R4") (pin "1") (pinfunction "1_1") (pintype "passive"))
      (node (ref "R5") (pin "2") (pinfunction "2_2") (pintype "passive"))
    )
    (net (code "47") (name "Net-(IC6-SS)") (class "Default")
      (node (ref "C3") (pin "2") (pinfunction "2_2") (pintype "passive"))
      (node (ref "IC6") (pin "8") (pinfunction "SS_8") (pintype "passive"))
    )
    (net (code "48") (name "Net-(IC6-SW)") (class "Default")
      (node (ref "C4") (pin "1") (pinfunction "1_1") (pintype "passive"))
      (node (ref "IC6") (pin "3") (pinfunction "SW_3") (pintype "passive"))
      (node (ref "L1") (pin "1") (pinfunction "1_1") (pintype "passive"))
    )
    (net (code "49") (name "Net-(IC6-VIN)") (class "Default")
      (node (ref "C1") (pin "2") (pinfunction "2_2") (pintype "passive"))
      (node (ref "C2") (pin "2") (pinfunction "2_2") (pintype "passive"))
      (node (ref "D1") (pin "C") (pinfunction "C_C") (pintype "passive"))
      (node (ref "D2") (pin "C") (pinfunction "C_C") (pintype "passive"))
      (node (ref "F1") (pin "1") (pinfunction "1_1") (pintype "passive"))
      (node (ref "IC6") (pin "2") (pinfunction "VIN_2") (pintype "power_in"))
      (node (ref "R1") (pin "2") (pinfunction "2_2") (pintype "passive"))
    )
    (net (code "50") (name "Net-(J1-Pad3)") (class "Default")
      (node (ref "J1") (pin "3") (pinfunction "3_3") (pintype "passive"))
      (node (ref "R24") (pin "1") (pinfunction "1_1") (pintype "passive"))
    )
    (net (code "51") (name "Net-(J2-Pad3)") (class "Default")
      (node (ref "J2") (pin "3") (pinfunction "3_3") (pintype "passive"))
      (node (ref "R27") (pin "1") (pinfunction "1_1") (pintype "passive"))
    )
    (net (code "52") (name "Net-(J3-Pad3)") (class "Default")
      (node (ref "J3") (pin "3") (pinfunction "3_3") (pintype "passive"))
      (node (ref "R30") (pin "1") (pinfunction "1_1") (pintype "passive"))
    )
    (net (code "53") (name "Net-(J4-Pad3)") (class "Default")
      (node (ref "J4") (pin "3") (pinfunction "3_3") (pintype "passive"))
      (node (ref "R33") (pin "1") (pinfunction "1_1") (pintype "passive"))
    )
    (net (code "54") (name "Net-(J5-Pad3)") (class "Default")
      (node (ref "J5") (pin "3") (pinfunction "3_3") (pintype "passive"))
      (node (ref "R36") (pin "1") (pinfunction "1_1") (pintype "passive"))
    )
    (net (code "55") (name "Net-(J6-Pad3)") (class "Default")
      (node (ref "J6") (pin "3") (pinfunction "3_3") (pintype "passive"))
      (node (ref "R39") (pin "1") (pinfunction "1_1") (pintype "passive"))
    )
    (net (code "56") (name "Net-(J7-Pad3)") (class "Default")
      (node (ref "J7") (pin "3") (pinfunction "3_3") (pintype "passive"))
      (node (ref "R42") (pin "1") (pinfunction "1_1") (pintype "passive"))
    )
    (net (code "57") (name "Net-(LED1-PadA)") (class "Default")
      (node (ref "LED1") (pin "A") (pinfunction "A_A") (pintype "passive"))
      (node (ref "R26") (pin "1") (pinfunction "1_1") (pintype "passive"))
    )
    (net (code "58") (name "Net-(LED2-PadA)") (class "Default")
      (node (ref "LED2") (pin "A") (pinfunction "A_A") (pintype "passive"))
      (node (ref "R29") (pin "1") (pinfunction "1_1") (pintype "passive"))
    )
    (net (code "59") (name "Net-(LED3-PadA)") (class "Default")
      (node (ref "LED3") (pin "A") (pinfunction "A_A") (pintype "passive"))
      (node (ref "R32") (pin "1") (pinfunction "1_1") (pintype "passive"))
    )
    (net (code "60") (name "Net-(LED4-PadA)") (class "Default")
      (node (ref "LED4") (pin "A") (pinfunction "A_A") (pintype "passive"))
      (node (ref "R35") (pin "1") (pinfunction "1_1") (pintype "passive"))
    )
    (net (code "61") (name "Net-(LED5-PadA)") (class "Default")
      (node (ref "LED5") (pin "A") (pinfunction "A_A") (pintype "passive"))
      (node (ref "R38") (pin "1") (pinfunction "1_1") (pintype "passive"))
    )
    (net (code "62") (name "Net-(LED6-PadA)") (class "Default")
      (node (ref "LED6") (pin "A") (pinfunction "A_A") (pintype "passive"))
      (node (ref "R41") (pin "1") (pinfunction "1_1") (pintype "passive"))
    )
    (net (code "63") (name "Net-(LED7-PadA)") (class "Default")
      (node (ref "LED7") (pin "A") (pinfunction "A_A") (pintype "passive"))
      (node (ref "R44") (pin "1") (pinfunction "1_1") (pintype "passive"))
    )
    (net (code "64") (name "Net-(LED8-PadA)") (class "Default")
      (node (ref "LED8") (pin "A") (pinfunction "A_A") (pintype "passive"))
      (node (ref "R22") (pin "2") (pinfunction "2_2") (pintype "passive"))
    )
    (net (code "65") (name "Net-(LED9-PadA)") (class "Default")
      (node (ref "LED9") (pin "A") (pinfunction "A_A") (pintype "passive"))
      (node (ref "R14") (pin "2") (pinfunction "2_2") (pintype "passive"))
    )
    (net (code "66") (name "Net-(LED16-PadA)") (class "Default")
      (node (ref "LED16") (pin "A") (pinfunction "A_A") (pintype "passive"))
      (node (ref "R10") (pin "2") (pinfunction "2_2") (pintype "passive"))
    )
    (net (code "67") (name "Net-(LED18-PadA)") (class "Default")
      (node (ref "LED18") (pin "A") (pinfunction "A_A") (pintype "passive"))
      (node (ref "R11") (pin "2") (pinfunction "2_2") (pintype "passive"))
    )
    (net (code "68") (name "Net-(R6-Pad2)") (class "Default")
      (node (ref "R6") (pin "2") (pinfunction "2_2") (pintype "passive"))
      (node (ref "USB") (pin "SHLD1") (pinfunction "SHIELD_SHLD1") (pintype "passive"))
      (node (ref "USB") (pin "SHLD2") (pinfunction "SHIELD_SHLD2") (pintype "passive"))
      (node (ref "USB") (pin "SHLD3") (pinfunction "SHIELD_SHLD3") (pintype "passive"))
    )
    (net (code "69") (name "Net-(R45-Pad2)") (class "Default")
      (node (ref "R45") (pin "2") (pinfunction "2_2") (pintype "passive"))
      (node (ref "RESET") (pin "2") (pinfunction "S1_2") (pintype "passive"))
      (node (ref "RESET") (pin "3") (pinfunction "S1_3") (pintype "passive"))
    )
    (net (code "70") (name "Net-(S1-2)") (class "Default")
      (node (ref "D6") (pin "A") (pinfunction "A_A") (pintype "passive"))
      (node (ref "S1") (pin "1") (pinfunction "2_1") (pintype "passive"))
      (node (ref "T2") (pin "3") (pinfunction "D_3") (pintype "passive"))
    )
    (net (code "71") (name "Net-(T1-D)") (class "Default")
      (node (ref "F2") (pin "2") (pinfunction "2_2") (pintype "passive"))
      (node (ref "T1") (pin "3") (pinfunction "D_3") (pintype "passive"))
    )
    (net (code "72") (name "Net-(T1-G)") (class "Default")
      (node (ref "R7") (pin "2") (pinfunction "2_2") (pintype "passive"))
      (node (ref "R8") (pin "1") (pinfunction "1_1") (pintype "passive"))
      (node (ref "T1") (pin "1") (pinfunction "G_1") (pintype "passive"))
    )
    (net (code "73") (name "Net-(T2-G)") (class "Default")
      (node (ref "R21") (pin "2") (pinfunction "2_2") (pintype "passive"))
      (node (ref "R22") (pin "1") (pinfunction "1_1") (pintype "passive"))
      (node (ref "R23") (pin "2") (pinfunction "2_2") (pintype "passive"))
      (node (ref "T2") (pin "1") (pinfunction "G_1") (pintype "passive"))
    )
    (net (code "74") (name "Net-(T4A-D)") (class "Default")
      (node (ref "LED6") (pin "C") (pinfunction "C_C") (pintype "passive"))
      (node (ref "T4") (pin "6") (pinfunction "D_6") (pintype "passive"))
    )
    (net (code "75") (name "Net-(T4B-D)") (class "Default")
      (node (ref "LED7") (pin "C") (pinfunction "C_C") (pintype "passive"))
      (node (ref "T4") (pin "3") (pinfunction "D_3") (pintype "passive"))
    )
    (net (code "76") (name "Net-(T5A-D)") (class "Default")
      (node (ref "LED4") (pin "C") (pinfunction "C_C") (pintype "passive"))
      (node (ref "T5") (pin "6") (pinfunction "D_6") (pintype "passive"))
    )
    (net (code "77") (name "Net-(T5B-D)") (class "Default")
      (node (ref "LED5") (pin "C") (pinfunction "C_C") (pintype "passive"))
      (node (ref "T5") (pin "3") (pinfunction "D_3") (pintype "passive"))
    )
    (net (code "78") (name "Net-(T6A-D)") (class "Default")
      (node (ref "LED2") (pin "C") (pinfunction "C_C") (pintype "passive"))
      (node (ref "T6") (pin "6") (pinfunction "D_6") (pintype "passive"))
    )
    (net (code "79") (name "Net-(T6B-D)") (class "Default")
      (node (ref "LED3") (pin "C") (pinfunction "C_C") (pintype "passive"))
      (node (ref "T6") (pin "3") (pinfunction "D_3") (pintype "passive"))
    )
    (net (code "80") (name "Net-(T7A-D)") (class "Default")
      (node (ref "LED1") (pin "C") (pinfunction "C_C") (pintype "passive"))
      (node (ref "T7") (pin "6") (pinfunction "D_6") (pintype "passive"))
    )
    (net (code "81") (name "RST") (class "Default")
      (node (ref "C14") (pin "2") (pinfunction "2_2") (pintype "passive"))
      (node (ref "IC1") (pin "24") (pinfunction "~{RESET}_24") (pintype "input"))
      (node (ref "R45") (pin "1") (pinfunction "1_1") (pintype "passive"))
      (node (ref "R9") (pin "2") (pinfunction "2_2") (pintype "passive"))
      (node (ref "RST") (pin "1") (pinfunction "P_1") (pintype "passive"))
    )
    (net (code "82") (name "RX_D13_LV") (class "Default")
      (node (ref "IC1") (pin "23") (pinfunction "(S5:3/T7:1)PB23_23") (pintype "bidirectional"))
      (node (ref "R20") (pin "1") (pinfunction "1_1") (pintype "passive"))
    )
    (net (code "83") (name "RX_HV") (class "Default")
      (node (ref "IC2") (pin "15") (pinfunction "A3_15") (pintype "input"))
      (node (ref "UART") (pin "4") (pinfunction "4_4") (pintype "passive"))
    )
    (net (code "84") (name "S1_SWDIO_D37") (class "Default")
      (node (ref "IC1") (pin "26") (pinfunction "(SWDIO/S1:3/T1:1)PA31_26") (pintype "bidirectional"))
      (node (ref "R21") (pin "1") (pinfunction "1_1") (pintype "passive"))
      (node (ref "SWDIO") (pin "1") (pinfunction "P_1") (pintype "passive"))
    )
    (net (code "85") (name "SCK_D9_LV") (class "Default")
      (node (ref "IC1") (pin "9") (pinfunction "(SCL/S1:1|3:1/T2:1|0:7)PA17_9") (pintype "bidirectional"))
      (node (ref "IC2") (pin "4") (pinfunction "A2_4") (pintype "input"))
    )
    (net (code "86") (name "SCK_HV") (class "Default")
      (node (ref "IC2") (pin "16") (pinfunction "Y2_16") (pintype "tri_state"))
      (node (ref "SPI") (pin "5") (pinfunction "5_5") (pintype "passive"))
    )
    (net (code "87") (name "SCL_D12_LV") (class "Default")
      (node (ref "IC1") (pin "39") (pinfunction "(SCL/S0:1|2:1/T0:1|1:3/AIN17)PA09_39") (pintype "bidirectional"))
      (node (ref "R15") (pin "1") (pinfunction "1_1") (pintype "passive"))
      (node (ref "T3") (pin "4") (pinfunction "S_4") (pintype "passive"))
    )
    (net (code "88") (name "SCL_HV") (class "Default")
      (node (ref "I2C/WIRE") (pin "4") (pinfunction "4_4") (pintype "passive"))
      (node (ref "I2C/WIRE.") (pin "4") (pinfunction "4_4") (pintype "passive"))
      (node (ref "R16") (pin "1") (pinfunction "1_1") (pintype "passive"))
      (node (ref "T3") (pin "3") (pinfunction "D_3") (pintype "passive"))
    )
    (net (code "89") (name "SDA_D11_LV") (class "Default")
      (node (ref "IC1") (pin "38") (pinfunction "(SDA/S0:0|2:0/T0:0|1:2/AIN16)PA08_38") (pintype "bidirectional"))
      (node (ref "R17") (pin "1") (pinfunction "1_1") (pintype "passive"))
      (node (ref "T3") (pin "1") (pinfunction "S_1") (pintype "passive"))
    )
    (net (code "90") (name "SDA_HV") (class "Default")
      (node (ref "I2C/WIRE") (pin "3") (pinfunction "3_3") (pintype "passive"))
      (node (ref "I2C/WIRE.") (pin "3") (pinfunction "3_3") (pintype "passive"))
      (node (ref "R18") (pin "1") (pinfunction "1_1") (pintype "passive"))
      (node (ref "T3") (pin "6") (pinfunction "D_6") (pintype "passive"))
    )
    (net (code "91") (name "TX_D14_LV") (class "Default")
      (node (ref "IC1") (pin "22") (pinfunction "(S5:2/T7:0)PB22_22") (pintype "bidirectional"))
      (node (ref "IC2") (pin "13") (pinfunction "A2_13") (pintype "input"))
    )
    (net (code "92") (name "TX_HV") (class "Default")
      (node (ref "IC2") (pin "7") (pinfunction "Y2_7") (pintype "tri_state"))
      (node (ref "UART") (pin "3") (pinfunction "3_3") (pintype "passive"))
    )
    (net (code "93") (name "USB_N") (class "Default")
      (node (ref "D-") (pin "1") (pinfunction "P_1") (pintype "passive"))
      (node (ref "D14") (pin "1") (pinfunction "C1_1") (pintype "passive"))
      (node (ref "IC1") (pin "18") (pinfunction "(USB_DM/S3:2|5:2/T5:0|1:2)PA24_18") (pintype "bidirectional"))
      (node (ref "USB") (pin "D-") (pinfunction "D-_D-") (pintype "bidirectional"))
    )
    (net (code "94") (name "USB_P") (class "Default")
      (node (ref "D+") (pin "1") (pinfunction "P_1") (pintype "passive"))
      (node (ref "D14") (pin "2") (pinfunction "C2_2") (pintype "passive"))
      (node (ref "IC1") (pin "19") (pinfunction "(USB_DP/S3:3|5:3/T5:1|1:3)PA25_19") (pintype "bidirectional"))
      (node (ref "USB") (pin "D+") (pinfunction "D+_D+") (pintype "bidirectional"))
    )
    (net (code "95") (name "V+") (class "Default")
      (node (ref "C19") (pin "1") (pinfunction "1_1") (pintype "passive"))
      (node (ref "C20") (pin "1") (pinfunction "1_1") (pintype "passive"))
      (node (ref "D6") (pin "C") (pinfunction "C_C") (pintype "passive"))
      (node (ref "F1") (pin "2") (pinfunction "2_2") (pintype "passive"))
      (node (ref "IC3") (pin "3") (pinfunction "VBB_3") (pintype "power_in"))
      (node (ref "IC4") (pin "3") (pinfunction "VBB_3") (pintype "power_in"))
      (node (ref "R12") (pin "1") (pinfunction "1_1") (pintype "passive"))
      (node (ref "S1") (pin "2") (pinfunction "1_2") (pintype "passive"))
    )
    (net (code "96") (name "VBUS") (class "Default")
      (node (ref "C10") (pin "2") (pinfunction "2_2") (pintype "passive"))
      (node (ref "F2") (pin "1") (pinfunction "1_1") (pintype "passive"))
      (node (ref "USB") (pin "VBUS") (pinfunction "VBUS_VBUS") (pintype "power_in"))
      (node (ref "VBUS") (pin "1") (pinfunction "P_1") (pintype "passive"))
    )
    (net (code "97") (name "VIN") (class "Default")
      (node (ref "D1") (pin "A") (pinfunction "A_A") (pintype "passive"))
      (node (ref "POWER") (pin "2") (pinfunction "1_2") (pintype "passive"))
      (node (ref "R8") (pin "2") (pinfunction "2_2") (pintype "passive"))
    )
    (net (code "98") (name "unconnected-(IC1-1{slash}RTC-Pad5)") (class "Default")
      (node (ref "IC1") (pin "5") (pinfunction "1/RTC_5") (pintype "bidirectional"))
    )
    (net (code "99") (name "unconnected-(IC1-3{slash}NC-Pad6)") (class "Default")
      (node (ref "IC1") (pin "6") (pinfunction "3/NC_6") (pintype "bidirectional"))
    )
    (net (code "100") (name "unconnected-(IC1-4{slash}15-Pad45)") (class "Default")
      (node (ref "IC1") (pin "45") (pinfunction "4/15_45") (pintype "bidirectional"))
    )
    (net (code "101") (name "unconnected-(IC1-CHIP_EN-Pad4)") (class "Default")
      (node (ref "IC1") (pin "4") (pinfunction "CHIP_EN_4") (pintype "input"))
    )
    (net (code "102") (name "unconnected-(IC1-RXD-Pad3)") (class "Default")
      (node (ref "IC1") (pin "3") (pinfunction "RXD_3") (pintype "input"))
    )
    (net (code "103") (name "unconnected-(IC1-SCL-Pad48)") (class "Default")
      (node (ref "IC1") (pin "48") (pinfunction "SCL_48") (pintype "bidirectional"))
    )
    (net (code "104") (name "unconnected-(IC1-SDA-Pad49)") (class "Default")
      (node (ref "IC1") (pin "49") (pinfunction "SDA_49") (pintype "bidirectional"))
    )
    (net (code "105") (name "unconnected-(IC1-TXD-Pad2)") (class "Default")
      (node (ref "IC1") (pin "2") (pinfunction "TXD_2") (pintype "output"))
    )
    (net (code "106") (name "unconnected-(IC1-W~{RESET}-Pad50)") (class "Default")
      (node (ref "IC1") (pin "50") (pinfunction "W~{RESET}_50") (pintype "input"))
    )
    (net (code "107") (name "unconnected-(IC2A-Y4-Pad12)") (class "Default")
      (node (ref "IC2") (pin "12") (pinfunction "Y4_12") (pintype "tri_state"))
    )
    (net (code "108") (name "unconnected-(IC2B-Y4-Pad3)") (class "Default")
      (node (ref "IC2") (pin "3") (pinfunction "Y4_3") (pintype "tri_state"))
    )
    (net (code "109") (name "unconnected-(USB-PadID)") (class "Default")
      (node (ref "USB") (pin "ID") (pinfunction "ID_ID") (pintype "bidirectional"))
    )
  )
)
